# ch340.net
KiCad netlist of a schematic drawn in EAGLE
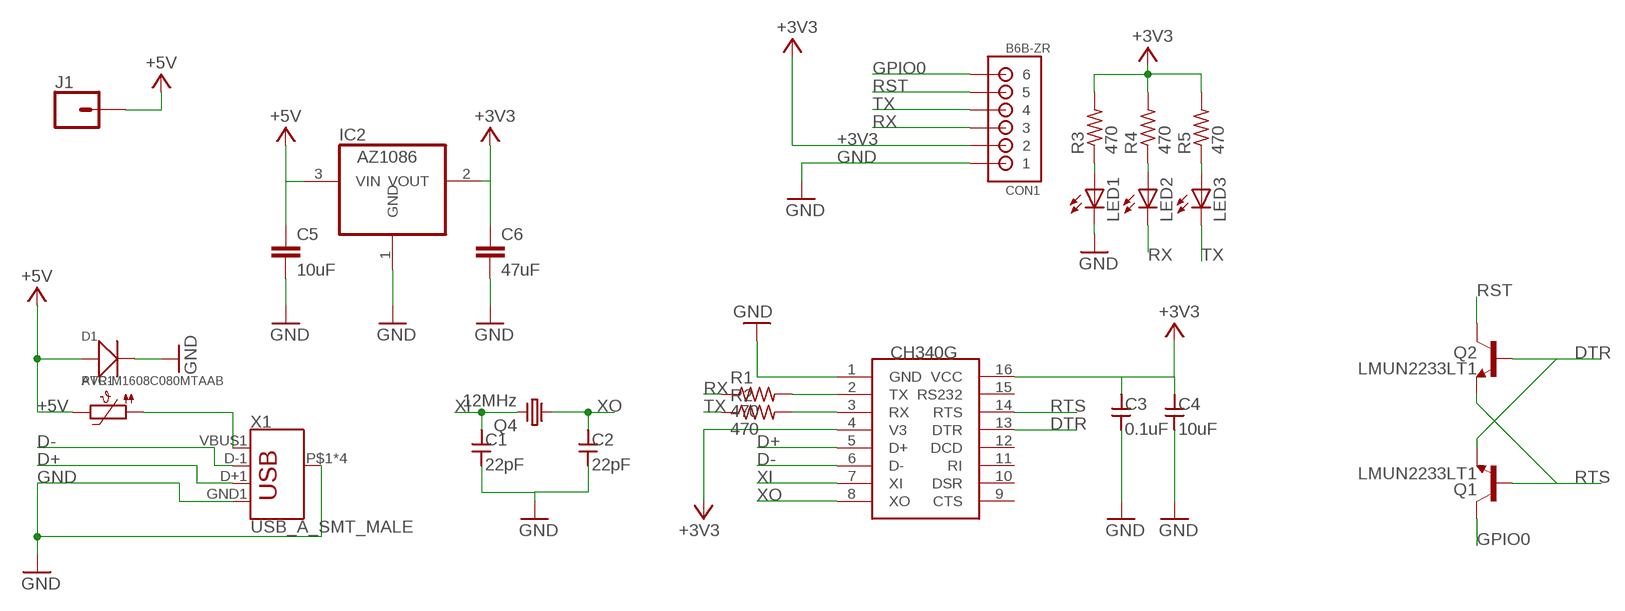
[diagram p0: schematic, sheet 1]

(export (version "E")
  (design (tool "Eeschema 10.0.6"))
  (components
    (comp (ref "C1")
      (value "22pF")
      (footprint "eagle-import:SMD1608")
      (libsource (lib "eagle-import") (part "CAPACITOR1608"))
    )
    (comp (ref "C2")
      (value "22pF")
      (footprint "eagle-import:SMD1608")
      (libsource (lib "eagle-import") (part "CAPACITOR1608"))
    )
    (comp (ref "C3")
      (value "0.1uF")
      (footprint "eagle-import:SMD1608")
      (libsource (lib "eagle-import") (part "CAPACITOR1608"))
    )
    (comp (ref "C4")
      (value "10uF")
      (footprint "eagle-import:SMD1608")
      (libsource (lib "eagle-import") (part "CAPACITOR1608"))
    )
    (comp (ref "C5")
      (value "10uF")
      (footprint "eagle-import:C0805")
      (libsource (lib "eagle-import") (part "C-EUC0805"))
    )
    (comp (ref "C6")
      (value "47uF")
      (footprint "eagle-import:C0805")
      (libsource (lib "eagle-import") (part "C-EUC0805"))
    )
    (comp (ref "CON1")
      (value "B6B-ZR")
      (footprint "eagle-import:B6B-ZR")
      (libsource (lib "eagle-import") (part "B6B-ZR"))
    )
    (comp (ref "D1")
      (value "AVR-M1608C080MTAAB")
      (footprint "eagle-import:TUMD2")
      (libsource (lib "eagle-import") (part "DIODETUMD2"))
    )
    (comp (ref "IC2")
      (value "AZ1086")
      (footprint "eagle-import:SOT223")
      (libsource (lib "eagle-import") (part "AZ1086"))
    )
    (comp (ref "J1")
      (value "CONN_01PTH_NO_SILK_YES_STOP")
      (footprint "eagle-import:1X01_NO_SILK")
      (libsource (lib "eagle-import") (part "CONN_01PTH_NO_SILK_YES_STOP"))
    )
    (comp (ref "LED1")
      (value "LEDCHIP-LED0805")
      (footprint "eagle-import:CHIP-LED0805")
      (libsource (lib "eagle-import") (part "LEDCHIP-LED0805"))
    )
    (comp (ref "LED2")
      (value "LEDCHIP-LED0805")
      (footprint "eagle-import:CHIP-LED0805")
      (libsource (lib "eagle-import") (part "LEDCHIP-LED0805"))
    )
    (comp (ref "LED3")
      (value "LEDCHIP-LED0805")
      (footprint "eagle-import:CHIP-LED0805")
      (libsource (lib "eagle-import") (part "LEDCHIP-LED0805"))
    )
    (comp (ref "PTC1")
      (value "PTC1206")
      (footprint "eagle-import:1206")
      (libsource (lib "eagle-import") (part "PTC1206"))
    )
    (comp (ref "Q1")
      (value "LMUN2233LT1")
      (footprint "eagle-import:SOT23-3")
      (libsource (lib "eagle-import") (part "LMUN2233LT1"))
    )
    (comp (ref "Q2")
      (value "LMUN2233LT1")
      (footprint "eagle-import:SOT23-3")
      (libsource (lib "eagle-import") (part "LMUN2233LT1"))
    )
    (comp (ref "Q4")
      (value "12MHz")
      (footprint "eagle-import:TC26H")
      (libsource (lib "eagle-import") (part "CRYSTAL-TC26H"))
    )
    (comp (ref "R1")
      (value "470")
      (footprint "eagle-import:R0603")
      (libsource (lib "eagle-import") (part "R-US_R0603"))
    )
    (comp (ref "R2")
      (value "470")
      (footprint "eagle-import:R0603")
      (libsource (lib "eagle-import") (part "R-US_R0603"))
    )
    (comp (ref "R3")
      (value "470")
      (footprint "eagle-import:R0603")
      (libsource (lib "eagle-import") (part "R-US_R0603"))
    )
    (comp (ref "R4")
      (value "470")
      (footprint "eagle-import:R0603")
      (libsource (lib "eagle-import") (part "R-US_R0603"))
    )
    (comp (ref "R5")
      (value "470")
      (footprint "eagle-import:R0603")
      (libsource (lib "eagle-import") (part "R-US_R0603"))
    )
    (comp (ref "U$1")
      (value "CH340G")
      (footprint "eagle-import:SOIC16")
      (libsource (lib "eagle-import") (part "CH340G"))
    )
    (comp (ref "X1")
      (value "USB_A_SMT_MALE")
      (footprint "eagle-import:USB-A-SMT-MALE")
      (libsource (lib "eagle-import") (part "USB_A_SMT_MALE"))
    )
  )
  (nets
    (net (code "1") (name "+3V3") (class "Default")
      (node (ref "C3") (pin "1") (pinfunction "1_1") (pintype "passive"))
      (node (ref "C4") (pin "1") (pinfunction "1_1") (pintype "passive"))
      (node (ref "C6") (pin "1") (pinfunction "1_1") (pintype "passive"))
      (node (ref "CON1") (pin "2") (pinfunction "2_2") (pintype "bidirectional"))
      (node (ref "IC2") (pin "2") (pinfunction "VOUT_2") (pintype "output"))
      (node (ref "R3") (pin "2") (pinfunction "2_2") (pintype "passive"))
      (node (ref "R4") (pin "2") (pinfunction "2_2") (pintype "passive"))
      (node (ref "R5") (pin "2") (pinfunction "2_2") (pintype "passive"))
      (node (ref "U$1") (pin "16") (pinfunction "VCC_16") (pintype "bidirectional"))
      (node (ref "U$1") (pin "4") (pinfunction "V3_4") (pintype "bidirectional"))
    )
    (net (code "2") (name "+5V") (class "Default")
      (node (ref "C5") (pin "1") (pinfunction "1_1") (pintype "passive"))
      (node (ref "D1") (pin "+") (pinfunction "+_+") (pintype "passive"))
      (node (ref "IC2") (pin "3") (pinfunction "VIN_3") (pintype "input"))
      (node (ref "J1") (pin "1") (pinfunction "1_1") (pintype "passive"))
      (node (ref "PTC1") (pin "2") (pinfunction "2_2") (pintype "passive"))
    )
    (net (code "3") (name "/D+") (class "Default")
      (node (ref "U$1") (pin "5") (pinfunction "D+_5") (pintype "bidirectional"))
      (node (ref "X1") (pin "D+1") (pinfunction "D+_D+1") (pintype "bidirectional"))
    )
    (net (code "4") (name "/D-") (class "Default")
      (node (ref "U$1") (pin "6") (pinfunction "D-_6") (pintype "bidirectional"))
      (node (ref "X1") (pin "D-1") (pinfunction "D-_D-1") (pintype "bidirectional"))
    )
    (net (code "5") (name "/DTR") (class "Default")
      (node (ref "Q1") (pin "3") (pinfunction "E_3") (pintype "passive"))
      (node (ref "Q2") (pin "1") (pinfunction "B_1") (pintype "passive"))
      (node (ref "U$1") (pin "13") (pinfunction "DTR_13") (pintype "bidirectional"))
    )
    (net (code "6") (name "/GPIO0") (class "Default")
      (node (ref "CON1") (pin "6") (pinfunction "6_6") (pintype "bidirectional"))
      (node (ref "Q1") (pin "2") (pinfunction "C_2") (pintype "passive"))
    )
    (net (code "7") (name "/RST") (class "Default")
      (node (ref "CON1") (pin "5") (pinfunction "5_5") (pintype "bidirectional"))
      (node (ref "Q2") (pin "2") (pinfunction "C_2") (pintype "passive"))
    )
    (net (code "8") (name "/RTS") (class "Default")
      (node (ref "Q1") (pin "1") (pinfunction "B_1") (pintype "passive"))
      (node (ref "Q2") (pin "3") (pinfunction "E_3") (pintype "passive"))
      (node (ref "U$1") (pin "14") (pinfunction "RTS_14") (pintype "bidirectional"))
    )
    (net (code "9") (name "/RX") (class "Default")
      (node (ref "CON1") (pin "3") (pinfunction "3_3") (pintype "bidirectional"))
      (node (ref "LED2") (pin "C") (pinfunction "C_C") (pintype "passive"))
      (node (ref "R1") (pin "1") (pinfunction "1_1") (pintype "passive"))
    )
    (net (code "10") (name "/TX") (class "Default")
      (node (ref "CON1") (pin "4") (pinfunction "4_4") (pintype "bidirectional"))
      (node (ref "LED3") (pin "C") (pinfunction "C_C") (pintype "passive"))
      (node (ref "R2") (pin "1") (pinfunction "1_1") (pintype "passive"))
    )
    (net (code "11") (name "/XI") (class "Default")
      (node (ref "C1") (pin "1") (pinfunction "1_1") (pintype "passive"))
      (node (ref "Q4") (pin "2") (pinfunction "2_2") (pintype "passive"))
      (node (ref "U$1") (pin "7") (pinfunction "XI_7") (pintype "bidirectional"))
    )
    (net (code "12") (name "/XO") (class "Default")
      (node (ref "C2") (pin "1") (pinfunction "1_1") (pintype "passive"))
      (node (ref "Q4") (pin "1") (pinfunction "1_1") (pintype "passive"))
      (node (ref "U$1") (pin "8") (pinfunction "XO_8") (pintype "bidirectional"))
    )
    (net (code "13") (name "GND") (class "Default")
      (node (ref "C1") (pin "2") (pinfunction "2_2") (pintype "passive"))
      (node (ref "C2") (pin "2") (pinfunction "2_2") (pintype "passive"))
      (node (ref "C3") (pin "2") (pinfunction "2_2") (pintype "passive"))
      (node (ref "C4") (pin "2") (pinfunction "2_2") (pintype "passive"))
      (node (ref "C5") (pin "2") (pinfunction "2_2") (pintype "passive"))
      (node (ref "C6") (pin "2") (pinfunction "2_2") (pintype "passive"))
      (node (ref "CON1") (pin "1") (pinfunction "1_1") (pintype "bidirectional"))
      (node (ref "D1") (pin "-") (pinfunction "-_-") (pintype "passive"))
      (node (ref "IC2") (pin "1") (pinfunction "GND_1") (pintype "power_in"))
      (node (ref "LED1") (pin "C") (pinfunction "C_C") (pintype "passive"))
      (node (ref "U$1") (pin "1") (pinfunction "GND_1") (pintype "bidirectional"))
      (node (ref "X1") (pin "GND1") (pinfunction "GND_GND1") (pintype "power_in"))
      (node (ref "X1") (pin "P$1") (pinfunction "SHIELD_P$1") (pintype "bidirectional"))
      (node (ref "X1") (pin "P$2") (pinfunction "SHIELD_P$2") (pintype "bidirectional"))
      (node (ref "X1") (pin "P$3") (pinfunction "SHIELD_P$3") (pintype "bidirectional"))
      (node (ref "X1") (pin "P$4") (pinfunction "SHIELD_P$4") (pintype "bidirectional"))
    )
    (net (code "14") (name "Net-(LED1-PadA)") (class "Default")
      (node (ref "LED1") (pin "A") (pinfunction "A_A") (pintype "passive"))
      (node (ref "R3") (pin "1") (pinfunction "1_1") (pintype "passive"))
    )
    (net (code "15") (name "Net-(LED2-PadA)") (class "Default")
      (node (ref "LED2") (pin "A") (pinfunction "A_A") (pintype "passive"))
      (node (ref "R4") (pin "1") (pinfunction "1_1") (pintype "passive"))
    )
    (net (code "16") (name "Net-(LED3-PadA)") (class "Default")
      (node (ref "LED3") (pin "A") (pinfunction "A_A") (pintype "passive"))
      (node (ref "R5") (pin "1") (pinfunction "1_1") (pintype "passive"))
    )
    (net (code "17") (name "Net-(U$1-RX)") (class "Default")
      (node (ref "R2") (pin "2") (pinfunction "2_2") (pintype "passive"))
      (node (ref "U$1") (pin "3") (pinfunction "RX_3") (pintype "bidirectional"))
    )
    (net (code "18") (name "Net-(U$1-TX)") (class "Default")
      (node (ref "R1") (pin "2") (pinfunction "2_2") (pintype "passive"))
      (node (ref "U$1") (pin "2") (pinfunction "TX_2") (pintype "bidirectional"))
    )
    (net (code "19") (name "Net-(X1-VBUS)") (class "Default")
      (node (ref "PTC1") (pin "1") (pinfunction "1_1") (pintype "passive"))
      (node (ref "X1") (pin "VBUS1") (pinfunction "VBUS_VBUS1") (pintype "power_in"))
    )
    (net (code "20") (name "unconnected-(U$1-CTS-Pad9)") (class "Default")
      (node (ref "U$1") (pin "9") (pinfunction "CTS_9") (pintype "bidirectional"))
    )
    (net (code "21") (name "unconnected-(U$1-DCD-Pad12)") (class "Default")
      (node (ref "U$1") (pin "12") (pinfunction "DCD_12") (pintype "bidirectional"))
    )
    (net (code "22") (name "unconnected-(U$1-DSR-Pad10)") (class "Default")
      (node (ref "U$1") (pin "10") (pinfunction "DSR_10") (pintype "bidirectional"))
    )
    (net (code "23") (name "unconnected-(U$1-RI-Pad11)") (class "Default")
      (node (ref "U$1") (pin "11") (pinfunction "RI_11") (pintype "bidirectional"))
    )
    (net (code "24") (name "unconnected-(U$1-RS232-Pad15)") (class "Default")
      (node (ref "U$1") (pin "15") (pinfunction "RS232_15") (pintype "bidirectional"))
    )
  )
)
